# cs301_YourGroupNumber---------------.net
KiCad netlist of a schematic drawn in Altium Designer
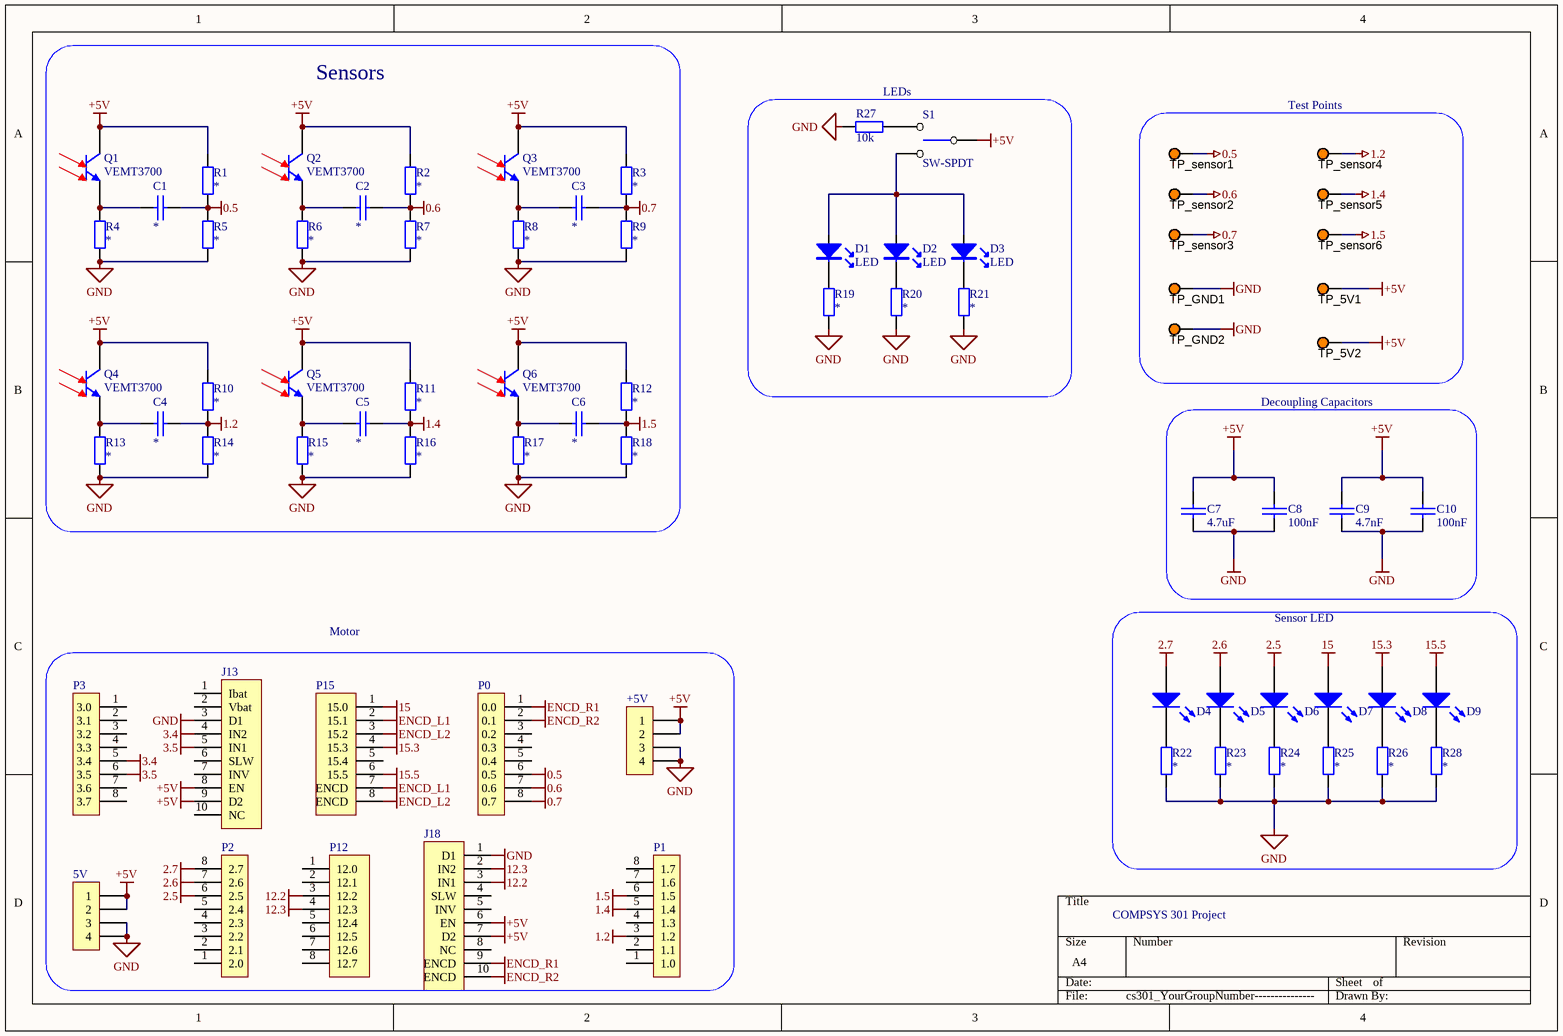
[diagram p0: cs301_YourGroupNumber---------------.SchDoc]

(export (version "E")
  (design (tool "Eeschema 10.0.6"))
  (components
    (comp (ref "+5V")
      (value "5V")
      (footprint "IDC4")
      (description "Connector")
      (libsource (lib "Miscellaneous Devices") (part "CON4"))
    )
    (comp (ref "5V")
      (value "5V")
      (footprint "IDC4")
      (description "Connector")
      (libsource (lib "Miscellaneous Devices") (part "CON4"))
    )
    (comp (ref "C1")
      (value "*")
      (footprint "0805 CAP")
      (description "SMT ceramic capacitor 0805 size")
      (libsource (lib "EE209_Library") (part "CerCap_SMT_0805"))
    )
    (comp (ref "C2")
      (value "*")
      (footprint "0805 CAP")
      (description "SMT ceramic capacitor 0805 size")
      (libsource (lib "EE209_Library") (part "CerCap_SMT_0805"))
    )
    (comp (ref "C3")
      (value "*")
      (footprint "0805 CAP")
      (description "SMT ceramic capacitor 0805 size")
      (libsource (lib "EE209_Library") (part "CerCap_SMT_0805"))
    )
    (comp (ref "C4")
      (value "*")
      (footprint "0805 CAP")
      (description "SMT ceramic capacitor 0805 size")
      (libsource (lib "EE209_Library") (part "CerCap_SMT_0805"))
    )
    (comp (ref "C5")
      (value "*")
      (footprint "0805 CAP")
      (description "SMT ceramic capacitor 0805 size")
      (libsource (lib "EE209_Library") (part "CerCap_SMT_0805"))
    )
    (comp (ref "C6")
      (value "*")
      (footprint "0805 CAP")
      (description "SMT ceramic capacitor 0805 size")
      (libsource (lib "EE209_Library") (part "CerCap_SMT_0805"))
    )
    (comp (ref "C7")
      (value "4.7uF")
      (footprint "0805 CAP")
      (description "SMT ceramic capacitor 0805 size")
      (libsource (lib "EE209_Library") (part "CerCap_SMT_0805"))
    )
    (comp (ref "C8")
      (value "100nF")
      (footprint "0805 CAP")
      (description "SMT ceramic capacitor 0805 size")
      (libsource (lib "EE209_Library") (part "CerCap_SMT_0805"))
    )
    (comp (ref "C9")
      (value "4.7nF")
      (footprint "0805 CAP")
      (description "SMT ceramic capacitor 0805 size")
      (libsource (lib "EE209_Library") (part "CerCap_SMT_0805"))
    )
    (comp (ref "C10")
      (value "100nF")
      (footprint "0805 CAP")
      (description "SMT ceramic capacitor 0805 size")
      (libsource (lib "EE209_Library") (part "CerCap_SMT_0805"))
    )
    (comp (ref "D1") (value "LED") (footprint "LED0.1/5MM") (libsource (lib "COMSYS301_2013") (part "LED")))
    (comp (ref "D2") (value "LED") (footprint "LED0.1/5MM") (libsource (lib "COMSYS301_2013") (part "LED")))
    (comp (ref "D3") (value "LED") (footprint "LED0.1/5MM") (libsource (lib "COMSYS301_2013") (part "LED")))
    (comp (ref "D4")
      (value "LTST-C170KGKT")
      (footprint "0805 LED")
      (description "SMT LED 0805 size")
      (fields (field (name "MANUFACTURER") "Lite-On Inc."))
      (libsource (lib "EE209_Library") (part "LED_SMT_0805"))
    )
    (comp (ref "D5")
      (value "LTST-C170KGKT")
      (footprint "0805 LED")
      (description "SMT LED 0805 size")
      (fields (field (name "MANUFACTURER") "Lite-On Inc."))
      (libsource (lib "EE209_Library") (part "LED_SMT_0805"))
    )
    (comp (ref "D6")
      (value "LTST-C170KGKT")
      (footprint "0805 LED")
      (description "SMT LED 0805 size")
      (fields (field (name "MANUFACTURER") "Lite-On Inc."))
      (libsource (lib "EE209_Library") (part "LED_SMT_0805"))
    )
    (comp (ref "D7")
      (value "LTST-C170KGKT")
      (footprint "0805 LED")
      (description "SMT LED 0805 size")
      (fields (field (name "MANUFACTURER") "Lite-On Inc."))
      (libsource (lib "EE209_Library") (part "LED_SMT_0805"))
    )
    (comp (ref "D8")
      (value "LTST-C170KGKT")
      (footprint "0805 LED")
      (description "SMT LED 0805 size")
      (fields (field (name "MANUFACTURER") "Lite-On Inc."))
      (libsource (lib "EE209_Library") (part "LED_SMT_0805"))
    )
    (comp (ref "D9")
      (value "LTST-C170KGKT")
      (footprint "0805 LED")
      (description "SMT LED 0805 size")
      (fields (field (name "MANUFACTURER") "Lite-On Inc."))
      (libsource (lib "EE209_Library") (part "LED_SMT_0805"))
    )
    (comp (ref "J13")
      (value "CON10")
      (footprint "idc10")
      (description "Connector")
      (libsource (lib "Miscellaneous Devices") (part "CON10"))
    )
    (comp (ref "J18")
      (value "CON10")
      (footprint "IDC10")
      (description "Connector")
      (libsource (lib "") (part "CON10_1"))
    )
    (comp (ref "P0")
      (value "P0")
      (footprint "idc8")
      (description "Connector")
      (libsource (lib "Miscellaneous Devices") (part "CON8"))
    )
    (comp (ref "P1")
      (value "P1")
      (footprint "idc8")
      (description "Connector")
      (libsource (lib "") (part "CON8_1"))
    )
    (comp (ref "P2")
      (value "P2")
      (footprint "idc8")
      (description "Connector")
      (libsource (lib "") (part "CON8_2"))
    )
    (comp (ref "P3")
      (value "P3")
      (footprint "idc8")
      (description "Connector")
      (libsource (lib "Miscellaneous Devices") (part "CON8"))
    )
    (comp (ref "P12")
      (value "P12")
      (footprint "idc8")
      (description "Connector")
      (libsource (lib "") (part "CON8_1_1"))
    )
    (comp (ref "P15")
      (value "P15")
      (footprint "idc8")
      (description "Connector")
      (libsource (lib "Miscellaneous Devices") (part "CON8_1"))
    )
    (comp (ref "Q1")
      (value "VEMT3700")
      (footprint "VEMT3700")
      (description "Silicon NPN Phototransistor")
      (libsource (lib "COMSYS301_2013") (part "VEMT3700"))
    )
    (comp (ref "Q2")
      (value "VEMT3700")
      (footprint "VEMT3700")
      (description "Silicon NPN Phototransistor")
      (libsource (lib "COMSYS301_2013") (part "VEMT3700"))
    )
    (comp (ref "Q3")
      (value "VEMT3700")
      (footprint "VEMT3700")
      (description "Silicon NPN Phototransistor")
      (libsource (lib "COMSYS301_2013") (part "VEMT3700"))
    )
    (comp (ref "Q4")
      (value "VEMT3700")
      (footprint "VEMT3700")
      (description "Silicon NPN Phototransistor")
      (libsource (lib "COMSYS301_2013") (part "VEMT3700"))
    )
    (comp (ref "Q5")
      (value "VEMT3700")
      (footprint "VEMT3700")
      (description "Silicon NPN Phototransistor")
      (libsource (lib "COMSYS301_2013") (part "VEMT3700"))
    )
    (comp (ref "Q6")
      (value "VEMT3700")
      (footprint "VEMT3700")
      (description "Silicon NPN Phototransistor")
      (libsource (lib "COMSYS301_2013") (part "VEMT3700"))
    )
    (comp (ref "R1")
      (value "*")
      (footprint "0805 RES")
      (description "0805 resistor")
      (fields (field (name "PUBLISHER") "Altium Limited"))
      (libsource (lib "EE209_Library") (part "Res_SMT_0805"))
    )
    (comp (ref "R2")
      (value "*")
      (footprint "0805 RES")
      (description "0805 resistor")
      (fields (field (name "PUBLISHER") "Altium Limited"))
      (libsource (lib "EE209_Library") (part "Res_SMT_0805"))
    )
    (comp (ref "R3")
      (value "*")
      (footprint "0805 RES")
      (description "0805 resistor")
      (fields (field (name "PUBLISHER") "Altium Limited"))
      (libsource (lib "EE209_Library") (part "Res_SMT_0805"))
    )
    (comp (ref "R4")
      (value "*")
      (footprint "0805 RES")
      (description "0805 resistor")
      (fields (field (name "PUBLISHER") "Altium Limited"))
      (libsource (lib "EE209_Library") (part "Res_SMT_0805"))
    )
    (comp (ref "R5")
      (value "*")
      (footprint "0805 RES")
      (description "0805 resistor")
      (fields (field (name "PUBLISHER") "Altium Limited"))
      (libsource (lib "EE209_Library") (part "Res_SMT_0805"))
    )
    (comp (ref "R6")
      (value "*")
      (footprint "0805 RES")
      (description "0805 resistor")
      (fields (field (name "PUBLISHER") "Altium Limited"))
      (libsource (lib "EE209_Library") (part "Res_SMT_0805"))
    )
    (comp (ref "R7")
      (value "*")
      (footprint "0805 RES")
      (description "0805 resistor")
      (fields (field (name "PUBLISHER") "Altium Limited"))
      (libsource (lib "EE209_Library") (part "Res_SMT_0805"))
    )
    (comp (ref "R8")
      (value "*")
      (footprint "0805 RES")
      (description "0805 resistor")
      (fields (field (name "PUBLISHER") "Altium Limited"))
      (libsource (lib "EE209_Library") (part "Res_SMT_0805"))
    )
    (comp (ref "R9")
      (value "*")
      (footprint "0805 RES")
      (description "0805 resistor")
      (fields (field (name "PUBLISHER") "Altium Limited"))
      (libsource (lib "EE209_Library") (part "Res_SMT_0805"))
    )
    (comp (ref "R10")
      (value "*")
      (footprint "0805 RES")
      (description "0805 resistor")
      (fields (field (name "PUBLISHER") "Altium Limited"))
      (libsource (lib "EE209_Library") (part "Res_SMT_0805"))
    )
    (comp (ref "R11")
      (value "*")
      (footprint "0805 RES")
      (description "0805 resistor")
      (fields (field (name "PUBLISHER") "Altium Limited"))
      (libsource (lib "EE209_Library") (part "Res_SMT_0805"))
    )
    (comp (ref "R12")
      (value "*")
      (footprint "0805 RES")
      (description "0805 resistor")
      (fields (field (name "PUBLISHER") "Altium Limited"))
      (libsource (lib "EE209_Library") (part "Res_SMT_0805"))
    )
    (comp (ref "R13")
      (value "*")
      (footprint "0805 RES")
      (description "0805 resistor")
      (fields (field (name "PUBLISHER") "Altium Limited"))
      (libsource (lib "EE209_Library") (part "Res_SMT_0805"))
    )
    (comp (ref "R14")
      (value "*")
      (footprint "0805 RES")
      (description "0805 resistor")
      (fields (field (name "PUBLISHER") "Altium Limited"))
      (libsource (lib "EE209_Library") (part "Res_SMT_0805"))
    )
    (comp (ref "R15")
      (value "*")
      (footprint "0805 RES")
      (description "0805 resistor")
      (fields (field (name "PUBLISHER") "Altium Limited"))
      (libsource (lib "EE209_Library") (part "Res_SMT_0805"))
    )
    (comp (ref "R16")
      (value "*")
      (footprint "0805 RES")
      (description "0805 resistor")
      (fields (field (name "PUBLISHER") "Altium Limited"))
      (libsource (lib "EE209_Library") (part "Res_SMT_0805"))
    )
    (comp (ref "R17")
      (value "*")
      (footprint "0805 RES")
      (description "0805 resistor")
      (fields (field (name "PUBLISHER") "Altium Limited"))
      (libsource (lib "EE209_Library") (part "Res_SMT_0805"))
    )
    (comp (ref "R18")
      (value "*")
      (footprint "0805 RES")
      (description "0805 resistor")
      (fields (field (name "PUBLISHER") "Altium Limited"))
      (libsource (lib "EE209_Library") (part "Res_SMT_0805"))
    )
    (comp (ref "R19")
      (value "*")
      (footprint "0805 RES")
      (description "0805 resistor")
      (fields (field (name "PUBLISHER") "Altium Limited"))
      (libsource (lib "EE209_Library") (part "Res_SMT_0805"))
    )
    (comp (ref "R20")
      (value "*")
      (footprint "0805 RES")
      (description "0805 resistor")
      (fields (field (name "PUBLISHER") "Altium Limited"))
      (libsource (lib "EE209_Library") (part "Res_SMT_0805"))
    )
    (comp (ref "R21")
      (value "*")
      (footprint "0805 RES")
      (description "0805 resistor")
      (fields (field (name "PUBLISHER") "Altium Limited"))
      (libsource (lib "EE209_Library") (part "Res_SMT_0805"))
    )
    (comp (ref "R22")
      (value "*")
      (footprint "0805 RES")
      (description "0805 resistor")
      (fields (field (name "PUBLISHER") "Altium Limited"))
      (libsource (lib "EE209_Library") (part "Res_SMT_0805"))
    )
    (comp (ref "R23")
      (value "*")
      (footprint "0805 RES")
      (description "0805 resistor")
      (fields (field (name "PUBLISHER") "Altium Limited"))
      (libsource (lib "EE209_Library") (part "Res_SMT_0805"))
    )
    (comp (ref "R24")
      (value "*")
      (footprint "0805 RES")
      (description "0805 resistor")
      (fields (field (name "PUBLISHER") "Altium Limited"))
      (libsource (lib "EE209_Library") (part "Res_SMT_0805"))
    )
    (comp (ref "R25")
      (value "*")
      (footprint "0805 RES")
      (description "0805 resistor")
      (fields (field (name "PUBLISHER") "Altium Limited"))
      (libsource (lib "EE209_Library") (part "Res_SMT_0805"))
    )
    (comp (ref "R26")
      (value "*")
      (footprint "0805 RES")
      (description "0805 resistor")
      (fields (field (name "PUBLISHER") "Altium Limited"))
      (libsource (lib "EE209_Library") (part "Res_SMT_0805"))
    )
    (comp (ref "R27")
      (value "10k")
      (footprint "0805 RES")
      (description "0805 resistor")
      (fields (field (name "PUBLISHER") "Altium Limited"))
      (libsource (lib "") (part "Res_SMT_0805_1"))
    )
    (comp (ref "R28")
      (value "*")
      (footprint "0805 RES")
      (description "0805 resistor")
      (fields (field (name "PUBLISHER") "Altium Limited"))
      (libsource (lib "EE209_Library") (part "Res_SMT_0805"))
    )
    (comp (ref "S1")
      (value "SW-SPDT")
      (footprint "SW-SPDT")
      (description "Toggle Switch")
      (libsource (lib "COMSYS301_2013") (part "SW-SPDT"))
    )
    (comp (ref "TP_5V1")
      (value "5003")
      (footprint "TP_TH")
      (description "Test Point, Orange, 1-Pin THD, RoHS")
      (libsource (lib "EE209_Library") (part "TestPoint"))
    )
    (comp (ref "TP_5V2")
      (value "5003")
      (footprint "TP_TH")
      (description "Test Point, Orange, 1-Pin THD, RoHS")
      (libsource (lib "EE209_Library") (part "TestPoint"))
    )
    (comp (ref "TP_GND1")
      (value "5003")
      (footprint "TP_TH")
      (description "Test Point, Orange, 1-Pin THD, RoHS")
      (libsource (lib "EE209_Library") (part "TestPoint"))
    )
    (comp (ref "TP_GND2")
      (value "5003")
      (footprint "TP_TH")
      (description "Test Point, Orange, 1-Pin THD, RoHS")
      (libsource (lib "EE209_Library") (part "TestPoint"))
    )
    (comp (ref "TP_sensor1")
      (value "5003")
      (footprint "TP_TH")
      (description "Test Point, Orange, 1-Pin THD, RoHS")
      (libsource (lib "EE209_Library") (part "TestPoint"))
    )
    (comp (ref "TP_sensor2")
      (value "5003")
      (footprint "TP_TH")
      (description "Test Point, Orange, 1-Pin THD, RoHS")
      (libsource (lib "EE209_Library") (part "TestPoint"))
    )
    (comp (ref "TP_sensor3")
      (value "5003")
      (footprint "TP_TH")
      (description "Test Point, Orange, 1-Pin THD, RoHS")
      (libsource (lib "EE209_Library") (part "TestPoint"))
    )
    (comp (ref "TP_sensor4")
      (value "5003")
      (footprint "TP_TH")
      (description "Test Point, Orange, 1-Pin THD, RoHS")
      (libsource (lib "EE209_Library") (part "TestPoint"))
    )
    (comp (ref "TP_sensor5")
      (value "5003")
      (footprint "TP_TH")
      (description "Test Point, Orange, 1-Pin THD, RoHS")
      (libsource (lib "EE209_Library") (part "TestPoint"))
    )
    (comp (ref "TP_sensor6")
      (value "5003")
      (footprint "TP_TH")
      (description "Test Point, Orange, 1-Pin THD, RoHS")
      (libsource (lib "EE209_Library") (part "TestPoint"))
    )
  )
  (nets
    (net (code "1") (name "+5V") (class "Default")
      (node (ref "+5V") (pin "1") (pinfunction "1_1") (pintype "passive"))
      (node (ref "+5V") (pin "2") (pinfunction "2_2") (pintype "passive"))
      (node (ref "5V") (pin "1") (pinfunction "1_1") (pintype "passive"))
      (node (ref "5V") (pin "2") (pinfunction "2_2") (pintype "passive"))
      (node (ref "C10") (pin "1") (pinfunction "1_1") (pintype "passive"))
      (node (ref "C7") (pin "1") (pinfunction "1_1") (pintype "passive"))
      (node (ref "C8") (pin "1") (pinfunction "1_1") (pintype "passive"))
      (node (ref "C9") (pin "1") (pinfunction "1_1") (pintype "passive"))
      (node (ref "J13") (pin "8") (pinfunction "EN_8") (pintype "passive"))
      (node (ref "J13") (pin "9") (pinfunction "D2_9") (pintype "passive"))
      (node (ref "J18") (pin "6") (pinfunction "EN_6") (pintype "passive"))
      (node (ref "J18") (pin "7") (pinfunction "D2_7") (pintype "passive"))
      (node (ref "Q1") (pin "1") (pinfunction "C_1") (pintype "passive"))
      (node (ref "Q2") (pin "1") (pinfunction "C_1") (pintype "passive"))
      (node (ref "Q3") (pin "1") (pinfunction "C_1") (pintype "passive"))
      (node (ref "Q4") (pin "1") (pinfunction "C_1") (pintype "passive"))
      (node (ref "Q5") (pin "1") (pinfunction "C_1") (pintype "passive"))
      (node (ref "Q6") (pin "1") (pinfunction "C_1") (pintype "passive"))
      (node (ref "R1") (pin "2") (pinfunction "2_2") (pintype "passive"))
      (node (ref "R10") (pin "2") (pinfunction "2_2") (pintype "passive"))
      (node (ref "R11") (pin "2") (pinfunction "2_2") (pintype "passive"))
      (node (ref "R12") (pin "2") (pinfunction "2_2") (pintype "passive"))
      (node (ref "R2") (pin "2") (pinfunction "2_2") (pintype "passive"))
      (node (ref "R3") (pin "2") (pinfunction "2_2") (pintype "passive"))
      (node (ref "S1") (pin "2") (pinfunction "2_2") (pintype "passive"))
      (node (ref "TP_5V1") (pin "1") (pinfunction "1_1") (pintype "passive"))
      (node (ref "TP_5V2") (pin "1") (pinfunction "1_1") (pintype "passive"))
    )
    (net (code "2") (name "0.5") (class "Default")
      (node (ref "C1") (pin "2") (pinfunction "2_2") (pintype "passive"))
      (node (ref "P0") (pin "6") (pinfunction "3.5_6") (pintype "passive"))
      (node (ref "R1") (pin "1") (pinfunction "1_1") (pintype "passive"))
      (node (ref "R5") (pin "2") (pinfunction "2_2") (pintype "passive"))
      (node (ref "TP_sensor1") (pin "1") (pinfunction "1_1") (pintype "passive"))
    )
    (net (code "3") (name "0.6") (class "Default")
      (node (ref "C2") (pin "2") (pinfunction "2_2") (pintype "passive"))
      (node (ref "P0") (pin "7") (pinfunction "3.6_7") (pintype "passive"))
      (node (ref "R2") (pin "1") (pinfunction "1_1") (pintype "passive"))
      (node (ref "R7") (pin "2") (pinfunction "2_2") (pintype "passive"))
      (node (ref "TP_sensor2") (pin "1") (pinfunction "1_1") (pintype "passive"))
    )
    (net (code "4") (name "0.7") (class "Default")
      (node (ref "C3") (pin "2") (pinfunction "2_2") (pintype "passive"))
      (node (ref "P0") (pin "8") (pinfunction "3.7_8") (pintype "passive"))
      (node (ref "R3") (pin "1") (pinfunction "1_1") (pintype "passive"))
      (node (ref "R9") (pin "2") (pinfunction "2_2") (pintype "passive"))
      (node (ref "TP_sensor3") (pin "1") (pinfunction "1_1") (pintype "passive"))
    )
    (net (code "5") (name "1.2") (class "Default")
      (node (ref "C4") (pin "2") (pinfunction "2_2") (pintype "passive"))
      (node (ref "P1") (pin "3") (pinfunction "1.2_3") (pintype "passive"))
      (node (ref "R10") (pin "1") (pinfunction "1_1") (pintype "passive"))
      (node (ref "R14") (pin "2") (pinfunction "2_2") (pintype "passive"))
      (node (ref "TP_sensor4") (pin "1") (pinfunction "1_1") (pintype "passive"))
    )
    (net (code "6") (name "1.4") (class "Default")
      (node (ref "C5") (pin "2") (pinfunction "2_2") (pintype "passive"))
      (node (ref "P1") (pin "5") (pinfunction "1.4_5") (pintype "passive"))
      (node (ref "R11") (pin "1") (pinfunction "1_1") (pintype "passive"))
      (node (ref "R16") (pin "2") (pinfunction "2_2") (pintype "passive"))
      (node (ref "TP_sensor5") (pin "1") (pinfunction "1_1") (pintype "passive"))
    )
    (net (code "7") (name "1.5") (class "Default")
      (node (ref "C6") (pin "2") (pinfunction "2_2") (pintype "passive"))
      (node (ref "P1") (pin "6") (pinfunction "1.5_6") (pintype "passive"))
      (node (ref "R12") (pin "1") (pinfunction "1_1") (pintype "passive"))
      (node (ref "R18") (pin "2") (pinfunction "2_2") (pintype "passive"))
      (node (ref "TP_sensor6") (pin "1") (pinfunction "1_1") (pintype "passive"))
    )
    (net (code "8") (name "2.5") (class "Default")
      (node (ref "D6") (pin "1") (pinfunction "A_1") (pintype "passive"))
      (node (ref "P2") (pin "6") (pinfunction "2.5_6") (pintype "passive"))
    )
    (net (code "9") (name "2.6") (class "Default")
      (node (ref "D5") (pin "1") (pinfunction "A_1") (pintype "passive"))
      (node (ref "P2") (pin "7") (pinfunction "2.6_7") (pintype "passive"))
    )
    (net (code "10") (name "2.7") (class "Default")
      (node (ref "D4") (pin "1") (pinfunction "A_1") (pintype "passive"))
      (node (ref "P2") (pin "8") (pinfunction "2.7_8") (pintype "passive"))
    )
    (net (code "11") (name "3.4") (class "Default")
      (node (ref "J13") (pin "4") (pinfunction "IN2_4") (pintype "passive"))
      (node (ref "P3") (pin "5") (pinfunction "3.4_5") (pintype "passive"))
    )
    (net (code "12") (name "3.5") (class "Default")
      (node (ref "J13") (pin "5") (pinfunction "IN1_5") (pintype "passive"))
      (node (ref "P3") (pin "6") (pinfunction "3.5_6") (pintype "passive"))
    )
    (net (code "13") (name "12.2") (class "Default")
      (node (ref "J18") (pin "3") (pinfunction "IN1_3") (pintype "passive"))
      (node (ref "P12") (pin "3") (pinfunction "12.2_3") (pintype "passive"))
    )
    (net (code "14") (name "12.3") (class "Default")
      (node (ref "J18") (pin "2") (pinfunction "IN2_2") (pintype "passive"))
      (node (ref "P12") (pin "4") (pinfunction "12.3_4") (pintype "passive"))
    )
    (net (code "15") (name "15") (class "Default")
      (node (ref "D7") (pin "1") (pinfunction "A_1") (pintype "passive"))
      (node (ref "P15") (pin "1") (pinfunction "15.0_1") (pintype "passive"))
    )
    (net (code "16") (name "15.3") (class "Default")
      (node (ref "D8") (pin "1") (pinfunction "A_1") (pintype "passive"))
      (node (ref "P15") (pin "4") (pinfunction "15.3_4") (pintype "passive"))
    )
    (net (code "17") (name "15.5") (class "Default")
      (node (ref "D9") (pin "1") (pinfunction "A_1") (pintype "passive"))
      (node (ref "P15") (pin "6") (pinfunction "15.5_6") (pintype "passive"))
    )
    (net (code "18") (name "ENCD_L1") (class "Default")
      (node (ref "P15") (pin "2") (pinfunction "15.1_2") (pintype "passive"))
      (node (ref "P15") (pin "7") (pinfunction "ENCD_7") (pintype "passive"))
    )
    (net (code "19") (name "ENCD_L2") (class "Default")
      (node (ref "P15") (pin "3") (pinfunction "15.2_3") (pintype "passive"))
      (node (ref "P15") (pin "8") (pinfunction "ENCD_8") (pintype "passive"))
    )
    (net (code "20") (name "ENCD_R1") (class "Default")
      (node (ref "J18") (pin "9") (pinfunction "ENCD_9") (pintype "passive"))
      (node (ref "P0") (pin "1") (pinfunction "3.0_1") (pintype "passive"))
    )
    (net (code "21") (name "ENCD_R2") (class "Default")
      (node (ref "J18") (pin "10") (pinfunction "ENCD_10") (pintype "passive"))
      (node (ref "P0") (pin "2") (pinfunction "3.1_2") (pintype "passive"))
    )
    (net (code "22") (name "GND") (class "Default")
      (node (ref "+5V") (pin "3") (pinfunction "3_3") (pintype "passive"))
      (node (ref "+5V") (pin "4") (pinfunction "4_4") (pintype "passive"))
      (node (ref "5V") (pin "3") (pinfunction "3_3") (pintype "passive"))
      (node (ref "5V") (pin "4") (pinfunction "4_4") (pintype "passive"))
      (node (ref "C10") (pin "2") (pinfunction "2_2") (pintype "passive"))
      (node (ref "C7") (pin "2") (pinfunction "2_2") (pintype "passive"))
      (node (ref "C8") (pin "2") (pinfunction "2_2") (pintype "passive"))
      (node (ref "C9") (pin "2") (pinfunction "2_2") (pintype "passive"))
      (node (ref "J13") (pin "3") (pinfunction "D1_3") (pintype "passive"))
      (node (ref "J18") (pin "1") (pinfunction "D1_1") (pintype "passive"))
      (node (ref "R13") (pin "1") (pinfunction "1_1") (pintype "passive"))
      (node (ref "R14") (pin "1") (pinfunction "1_1") (pintype "passive"))
      (node (ref "R15") (pin "1") (pinfunction "1_1") (pintype "passive"))
      (node (ref "R16") (pin "1") (pinfunction "1_1") (pintype "passive"))
      (node (ref "R17") (pin "1") (pinfunction "1_1") (pintype "passive"))
      (node (ref "R18") (pin "1") (pinfunction "1_1") (pintype "passive"))
      (node (ref "R19") (pin "1") (pinfunction "1_1") (pintype "passive"))
      (node (ref "R20") (pin "1") (pinfunction "1_1") (pintype "passive"))
      (node (ref "R21") (pin "1") (pinfunction "1_1") (pintype "passive"))
      (node (ref "R22") (pin "1") (pinfunction "1_1") (pintype "passive"))
      (node (ref "R23") (pin "1") (pinfunction "1_1") (pintype "passive"))
      (node (ref "R24") (pin "1") (pinfunction "1_1") (pintype "passive"))
      (node (ref "R25") (pin "1") (pinfunction "1_1") (pintype "passive"))
      (node (ref "R26") (pin "1") (pinfunction "1_1") (pintype "passive"))
      (node (ref "R27") (pin "1") (pinfunction "1_1") (pintype "passive"))
      (node (ref "R28") (pin "1") (pinfunction "1_1") (pintype "passive"))
      (node (ref "R4") (pin "1") (pinfunction "1_1") (pintype "passive"))
      (node (ref "R5") (pin "1") (pinfunction "1_1") (pintype "passive"))
      (node (ref "R6") (pin "1") (pinfunction "1_1") (pintype "passive"))
      (node (ref "R7") (pin "1") (pinfunction "1_1") (pintype "passive"))
      (node (ref "R8") (pin "1") (pinfunction "1_1") (pintype "passive"))
      (node (ref "R9") (pin "1") (pinfunction "1_1") (pintype "passive"))
      (node (ref "TP_GND1") (pin "1") (pinfunction "1_1") (pintype "passive"))
      (node (ref "TP_GND2") (pin "1") (pinfunction "1_1") (pintype "passive"))
    )
    (net (code "23") (name "Net-(D1-1)") (class "Default")
      (node (ref "D1") (pin "A") (pinfunction "1_A") (pintype "passive"))
      (node (ref "D2") (pin "A") (pinfunction "1_A") (pintype "passive"))
      (node (ref "D3") (pin "A") (pinfunction "1_A") (pintype "passive"))
      (node (ref "S1") (pin "1") (pinfunction "1_1") (pintype "passive"))
    )
    (net (code "24") (name "Net-(D1-2)") (class "Default")
      (node (ref "D1") (pin "K") (pinfunction "2_K") (pintype "passive"))
      (node (ref "R19") (pin "2") (pinfunction "2_2") (pintype "passive"))
    )
    (net (code "25") (name "Net-(D2-2)") (class "Default")
      (node (ref "D2") (pin "K") (pinfunction "2_K") (pintype "passive"))
      (node (ref "R20") (pin "2") (pinfunction "2_2") (pintype "passive"))
    )
    (net (code "26") (name "Net-(D3-2)") (class "Default")
      (node (ref "D3") (pin "K") (pinfunction "2_K") (pintype "passive"))
      (node (ref "R21") (pin "2") (pinfunction "2_2") (pintype "passive"))
    )
    (net (code "27") (name "Net-(D4-K)") (class "Default")
      (node (ref "D4") (pin "2") (pinfunction "K_2") (pintype "passive"))
      (node (ref "R22") (pin "2") (pinfunction "2_2") (pintype "passive"))
    )
    (net (code "28") (name "Net-(D5-K)") (class "Default")
      (node (ref "D5") (pin "2") (pinfunction "K_2") (pintype "passive"))
      (node (ref "R23") (pin "2") (pinfunction "2_2") (pintype "passive"))
    )
    (net (code "29") (name "Net-(D6-K)") (class "Default")
      (node (ref "D6") (pin "2") (pinfunction "K_2") (pintype "passive"))
      (node (ref "R24") (pin "2") (pinfunction "2_2") (pintype "passive"))
    )
    (net (code "30") (name "Net-(D7-K)") (class "Default")
      (node (ref "D7") (pin "2") (pinfunction "K_2") (pintype "passive"))
      (node (ref "R25") (pin "2") (pinfunction "2_2") (pintype "passive"))
    )
    (net (code "31") (name "Net-(D8-K)") (class "Default")
      (node (ref "D8") (pin "2") (pinfunction "K_2") (pintype "passive"))
      (node (ref "R26") (pin "2") (pinfunction "2_2") (pintype "passive"))
    )
    (net (code "32") (name "Net-(D9-K)") (class "Default")
      (node (ref "D9") (pin "2") (pinfunction "K_2") (pintype "passive"))
      (node (ref "R28") (pin "2") (pinfunction "2_2") (pintype "passive"))
    )
    (net (code "33") (name "Net-(Q1-E)") (class "Default")
      (node (ref "C1") (pin "1") (pinfunction "1_1") (pintype "passive"))
      (node (ref "Q1") (pin "2") (pinfunction "E_2") (pintype "passive"))
      (node (ref "R4") (pin "2") (pinfunction "2_2") (pintype "passive"))
    )
    (net (code "34") (name "Net-(Q2-E)") (class "Default")
      (node (ref "C2") (pin "1") (pinfunction "1_1") (pintype "passive"))
      (node (ref "Q2") (pin "2") (pinfunction "E_2") (pintype "passive"))
      (node (ref "R6") (pin "2") (pinfunction "2_2") (pintype "passive"))
    )
    (net (code "35") (name "Net-(Q3-E)") (class "Default")
      (node (ref "C3") (pin "1") (pinfunction "1_1") (pintype "passive"))
      (node (ref "Q3") (pin "2") (pinfunction "E_2") (pintype "passive"))
      (node (ref "R8") (pin "2") (pinfunction "2_2") (pintype "passive"))
    )
    (net (code "36") (name "Net-(Q4-E)") (class "Default")
      (node (ref "C4") (pin "1") (pinfunction "1_1") (pintype "passive"))
      (node (ref "Q4") (pin "2") (pinfunction "E_2") (pintype "passive"))
      (node (ref "R13") (pin "2") (pinfunction "2_2") (pintype "passive"))
    )
    (net (code "37") (name "Net-(Q5-E)") (class "Default")
      (node (ref "C5") (pin "1") (pinfunction "1_1") (pintype "passive"))
      (node (ref "Q5") (pin "2") (pinfunction "E_2") (pintype "passive"))
      (node (ref "R15") (pin "2") (pinfunction "2_2") (pintype "passive"))
    )
    (net (code "38") (name "Net-(Q6-E)") (class "Default")
      (node (ref "C6") (pin "1") (pinfunction "1_1") (pintype "passive"))
      (node (ref "Q6") (pin "2") (pinfunction "E_2") (pintype "passive"))
      (node (ref "R17") (pin "2") (pinfunction "2_2") (pintype "passive"))
    )
    (net (code "39") (name "Net-(R27-Pad2)") (class "Default")
      (node (ref "R27") (pin "2") (pinfunction "2_2") (pintype "passive"))
      (node (ref "S1") (pin "3") (pinfunction "3_3") (pintype "passive"))
    )
    (net (code "40") (name "unconnected-(J13-INV-Pad7)") (class "Default")
      (node (ref "J13") (pin "7") (pinfunction "INV_7") (pintype "passive"))
    )
    (net (code "41") (name "unconnected-(J13-Ibat-Pad1)") (class "Default")
      (node (ref "J13") (pin "1") (pinfunction "Ibat_1") (pintype "passive"))
    )
    (net (code "42") (name "unconnected-(J13-NC-Pad10)") (class "Default")
      (node (ref "J13") (pin "10") (pinfunction "NC_10") (pintype "passive"))
    )
    (net (code "43") (name "unconnected-(J13-SLW-Pad6)") (class "Default")
      (node (ref "J13") (pin "6") (pinfunction "SLW_6") (pintype "passive"))
    )
    (net (code "44") (name "unconnected-(J13-Vbat-Pad2)") (class "Default")
      (node (ref "J13") (pin "2") (pinfunction "Vbat_2") (pintype "passive"))
    )
    (net (code "45") (name "unconnected-(J18-INV-Pad5)") (class "Default")
      (node (ref "J18") (pin "5") (pinfunction "INV_5") (pintype "passive"))
    )
    (net (code "46") (name "unconnected-(J18-NC-Pad8)") (class "Default")
      (node (ref "J18") (pin "8") (pinfunction "NC_8") (pintype "passive"))
    )
    (net (code "47") (name "unconnected-(J18-SLW-Pad4)") (class "Default")
      (node (ref "J18") (pin "4") (pinfunction "SLW_4") (pintype "passive"))
    )
    (net (code "48") (name "unconnected-(P0-3.2-Pad3)") (class "Default")
      (node (ref "P0") (pin "3") (pinfunction "3.2_3") (pintype "passive"))
    )
    (net (code "49") (name "unconnected-(P0-3.3-Pad4)") (class "Default")
      (node (ref "P0") (pin "4") (pinfunction "3.3_4") (pintype "passive"))
    )
    (net (code "50") (name "unconnected-(P0-3.4-Pad5)") (class "Default")
      (node (ref "P0") (pin "5") (pinfunction "3.4_5") (pintype "passive"))
    )
    (net (code "51") (name "unconnected-(P1-1.0-Pad1)") (class "Default")
      (node (ref "P1") (pin "1") (pinfunction "1.0_1") (pintype "passive"))
    )
    (net (code "52") (name "unconnected-(P1-1.1-Pad2)") (class "Default")
      (node (ref "P1") (pin "2") (pinfunction "1.1_2") (pintype "passive"))
    )
    (net (code "53") (name "unconnected-(P1-1.3-Pad4)") (class "Default")
      (node (ref "P1") (pin "4") (pinfunction "1.3_4") (pintype "passive"))
    )
    (net (code "54") (name "unconnected-(P1-1.6-Pad7)") (class "Default")
      (node (ref "P1") (pin "7") (pinfunction "1.6_7") (pintype "passive"))
    )
    (net (code "55") (name "unconnected-(P1-1.7-Pad8)") (class "Default")
      (node (ref "P1") (pin "8") (pinfunction "1.7_8") (pintype "passive"))
    )
    (net (code "56") (name "unconnected-(P2-2.0-Pad1)") (class "Default")
      (node (ref "P2") (pin "1") (pinfunction "2.0_1") (pintype "passive"))
    )
    (net (code "57") (name "unconnected-(P2-2.1-Pad2)") (class "Default")
      (node (ref "P2") (pin "2") (pinfunction "2.1_2") (pintype "passive"))
    )
    (net (code "58") (name "unconnected-(P2-2.2-Pad3)") (class "Default")
      (node (ref "P2") (pin "3") (pinfunction "2.2_3") (pintype "passive"))
    )
    (net (code "59") (name "unconnected-(P2-2.3-Pad4)") (class "Default")
      (node (ref "P2") (pin "4") (pinfunction "2.3_4") (pintype "passive"))
    )
    (net (code "60") (name "unconnected-(P2-2.4-Pad5)") (class "Default")
      (node (ref "P2") (pin "5") (pinfunction "2.4_5") (pintype "passive"))
    )
    (net (code "61") (name "unconnected-(P3-3.0-Pad1)") (class "Default")
      (node (ref "P3") (pin "1") (pinfunction "3.0_1") (pintype "passive"))
    )
    (net (code "62") (name "unconnected-(P3-3.1-Pad2)") (class "Default")
      (node (ref "P3") (pin "2") (pinfunction "3.1_2") (pintype "passive"))
    )
    (net (code "63") (name "unconnected-(P3-3.2-Pad3)") (class "Default")
      (node (ref "P3") (pin "3") (pinfunction "3.2_3") (pintype "passive"))
    )
    (net (code "64") (name "unconnected-(P3-3.3-Pad4)") (class "Default")
      (node (ref "P3") (pin "4") (pinfunction "3.3_4") (pintype "passive"))
    )
    (net (code "65") (name "unconnected-(P3-3.6-Pad7)") (class "Default")
      (node (ref "P3") (pin "7") (pinfunction "3.6_7") (pintype "passive"))
    )
    (net (code "66") (name "unconnected-(P3-3.7-Pad8)") (class "Default")
      (node (ref "P3") (pin "8") (pinfunction "3.7_8") (pintype "passive"))
    )
    (net (code "67") (name "unconnected-(P12-12.0-Pad1)") (class "Default")
      (node (ref "P12") (pin "1") (pinfunction "12.0_1") (pintype "passive"))
    )
    (net (code "68") (name "unconnected-(P12-12.1-Pad2)") (class "Default")
      (node (ref "P12") (pin "2") (pinfunction "12.1_2") (pintype "passive"))
    )
    (net (code "69") (name "unconnected-(P12-12.4-Pad5)") (class "Default")
      (node (ref "P12") (pin "5") (pinfunction "12.4_5") (pintype "passive"))
    )
    (net (code "70") (name "unconnected-(P12-12.5-Pad6)") (class "Default")
      (node (ref "P12") (pin "6") (pinfunction "12.5_6") (pintype "passive"))
    )
    (net (code "71") (name "unconnected-(P12-12.6-Pad7)") (class "Default")
      (node (ref "P12") (pin "7") (pinfunction "12.6_7") (pintype "passive"))
    )
    (net (code "72") (name "unconnected-(P12-12.7-Pad8)") (class "Default")
      (node (ref "P12") (pin "8") (pinfunction "12.7_8") (pintype "passive"))
    )
    (net (code "73") (name "unconnected-(P15-15.4-Pad5)") (class "Default")
      (node (ref "P15") (pin "5") (pinfunction "15.4_5") (pintype "passive"))
    )
  )
)
